# Sensorunit.net
KiCad netlist of a schematic drawn in Altium Designer
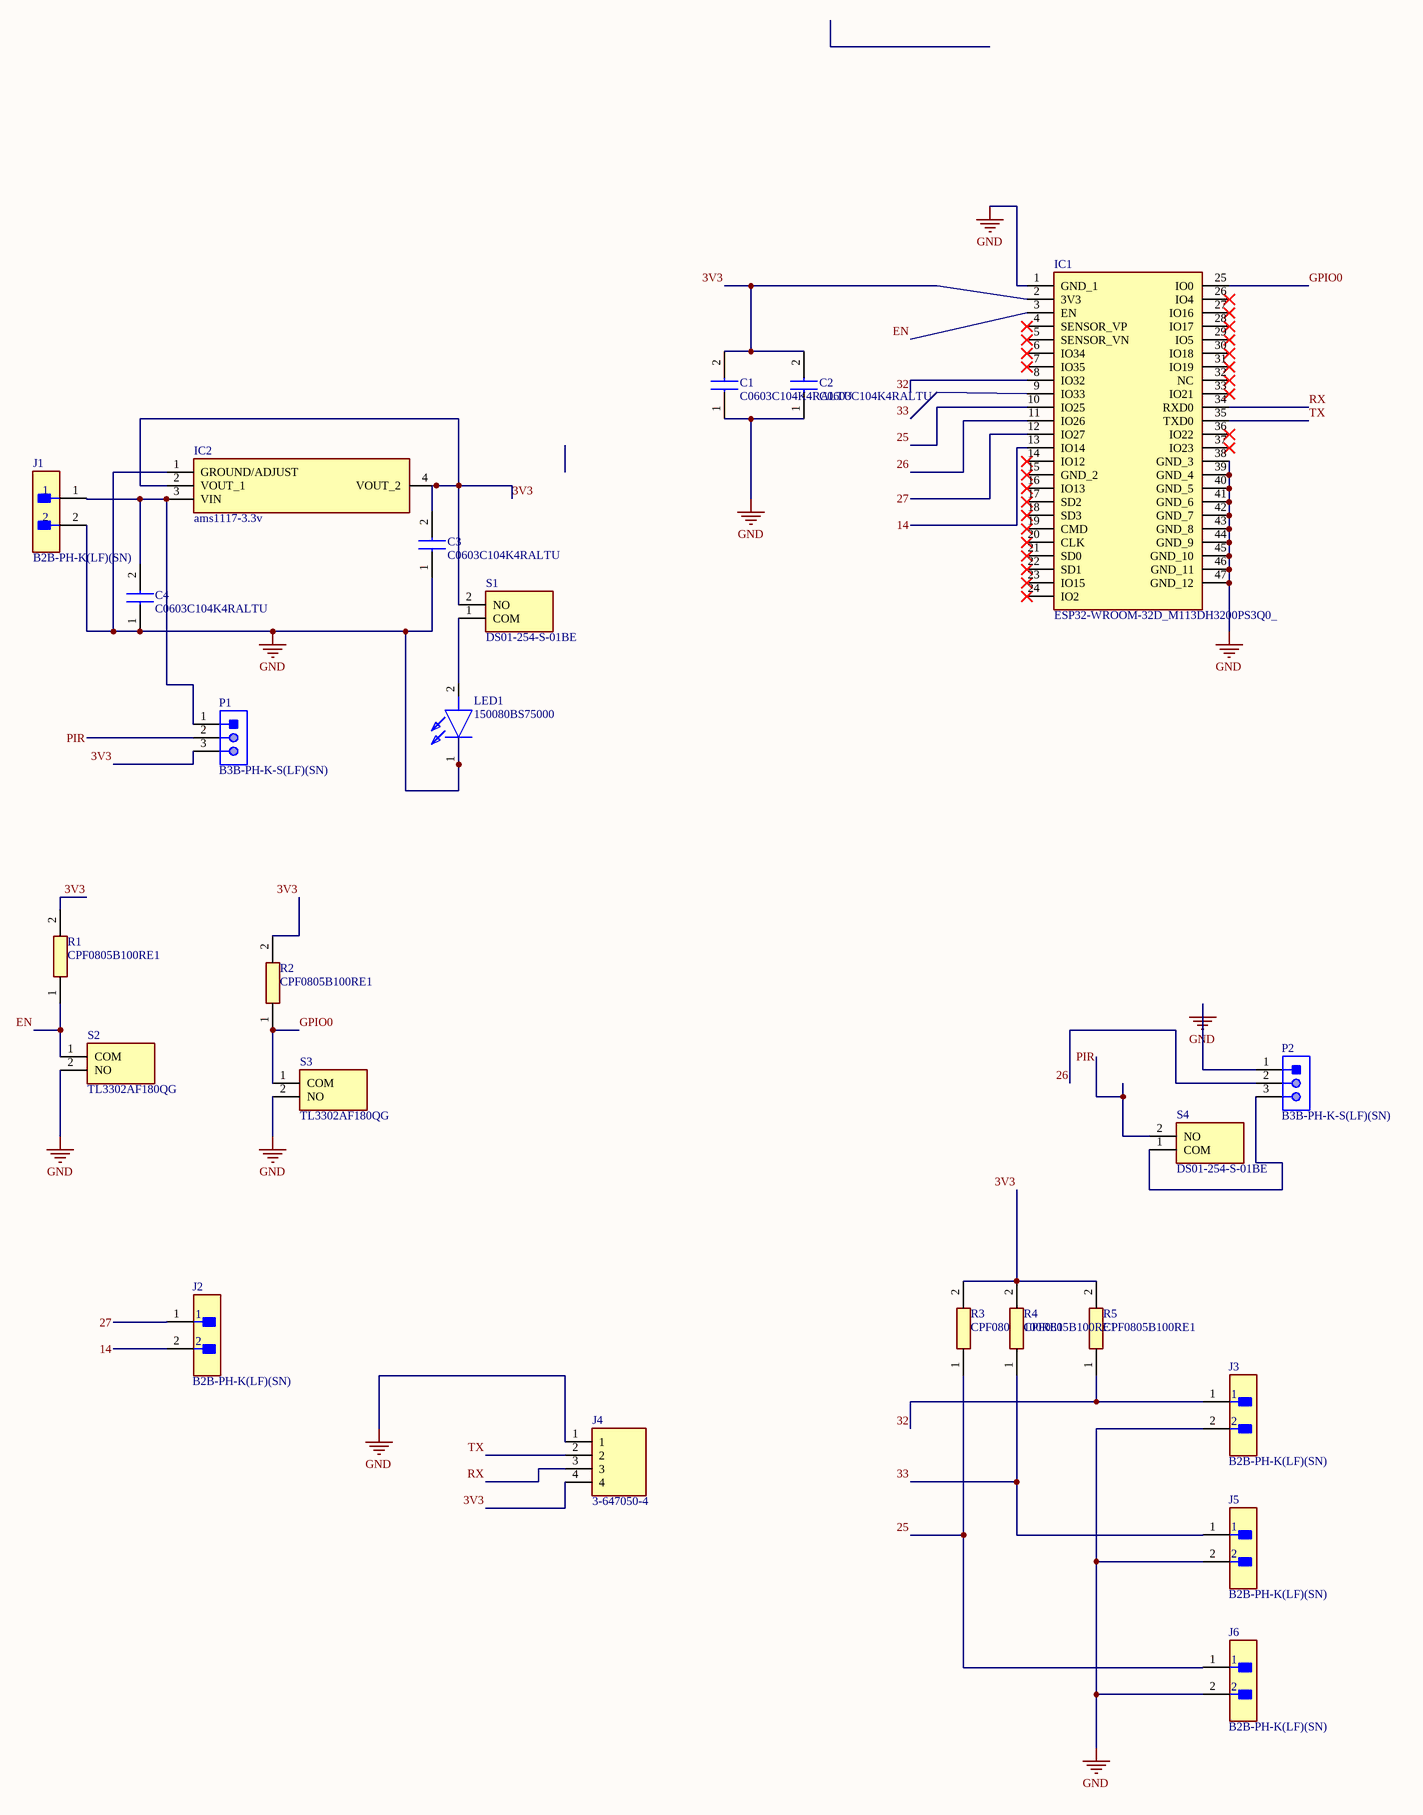
[diagram p0: Sensorunit.SchDoc]

(export (version "E")
  (design (tool "Eeschema 10.0.6"))
  (components
    (comp (ref "C1")
      (value "C0603C104K4RALTU")
      (footprint "SamacSys:C0603")
      (description "Capacitor")
      (fields (field (name "MOUSER PART NUMBER") "80-C0603C104K4RAL"))
      (libsource (lib "SamacSys") (part "C0603C104K4RALTU"))
    )
    (comp (ref "C2")
      (value "C0603C104K4RALTU")
      (footprint "SamacSys:C0603")
      (description "Capacitor")
      (fields (field (name "MOUSER PART NUMBER") "80-C0603C104K4RAL"))
      (libsource (lib "SamacSys") (part "C0603C104K4RALTU"))
    )
    (comp (ref "C3")
      (value "C0603C104K4RALTU")
      (footprint "SamacSys:C0603")
      (description "Capacitor")
      (fields (field (name "MOUSER PART NUMBER") "80-C0603C104K4RAL"))
      (libsource (lib "SamacSys") (part "C0603C104K4RALTU"))
    )
    (comp (ref "C4")
      (value "C0603C104K4RALTU")
      (footprint "SamacSys:C0603")
      (description "Capacitor")
      (fields (field (name "MOUSER PART NUMBER") "80-C0603C104K4RAL"))
      (libsource (lib "SamacSys") (part "C0603C104K4RALTU"))
    )
    (comp (ref "IC1")
      (value "ESP32-WROOM-32D_M113DH3200PS3Q0_")
      (footprint "SamacSys:ESP32WROOM32DM113DH3200PS3Q0")
      (description "Integrated Circuit")
      (fields
        (field (name "MANUFACTURER_PART_NUMBER") "ESP32-WROOM-32D(M113DH3200PS3Q0)")
        (field (name "MOUSER PART NUMBER") "356-ESPWROOM3200PS3")
      )
      (libsource (lib "SamacSys") (part "ESP32-WROOM-32D_M113DH3200PS3Q0_"))
    )
    (comp (ref "IC2")
      (value "ams1117-3.3v")
      (footprint "SamacSys:SOT229P700X180-4N")
      (description "Integrated Circuit")
      (libsource (lib "*") (part "ams1117-3.3v"))
    )
    (comp (ref "J1")
      (value "B2B-PH-K(LF)(SN)")
      (footprint "FP-B2B-PH-K_LF_SN-MFG")
      (description "Connector Header Through Hole 2 position 0.079\" (2.00mm)")
      (libsource (lib "") (part "3bc925449376181038e59eaffc5286c_1"))
    )
    (comp (ref "J2")
      (value "B2B-PH-K(LF)(SN)")
      (footprint "FP-B2B-PH-K_LF_SN-MFG")
      (description "Connector Header Through Hole 2 position 0.079\" (2.00mm)")
      (libsource (lib "Altium Content Vault") (part "3bc925449376181038e59eaffc5286c"))
    )
    (comp (ref "J3")
      (value "B2B-PH-K(LF)(SN)")
      (footprint "FP-B2B-PH-K_LF_SN-MFG")
      (description "Connector Header Through Hole 2 position 0.079\" (2.00mm)")
      (libsource (lib "Altium Content Vault") (part "3bc925449376181038e59eaffc5286c"))
    )
    (comp (ref "J4")
      (value "3-647050-4")
      (footprint "SamacSys:SHDR4W66P0X254_1X4_1016X635X1079P")
      (description "Connector")
      (fields (field (name "MOUSER PART NUMBER") "571-3-647050-4"))
      (libsource (lib "SamacSys") (part "3-647050-4"))
    )
    (comp (ref "J5")
      (value "B2B-PH-K(LF)(SN)")
      (footprint "FP-B2B-PH-K_LF_SN-MFG")
      (description "Connector Header Through Hole 2 position 0.079\" (2.00mm)")
      (libsource (lib "Altium Content Vault") (part "3bc925449376181038e59eaffc5286c"))
    )
    (comp (ref "J6")
      (value "B2B-PH-K(LF)(SN)")
      (footprint "FP-B2B-PH-K_LF_SN-MFG")
      (description "Connector Header Through Hole 2 position 0.079\" (2.00mm)")
      (libsource (lib "Altium Content Vault") (part "3bc925449376181038e59eaffc5286c"))
    )
    (comp (ref "LED1")
      (value "150080BS75000")
      (footprint "SamacSys:LEDC2012X80N")
      (description "LED")
      (fields (field (name "MOUSER PART NUMBER") "710-150080BS75000"))
      (libsource (lib "SamacSys") (part "150080BS75000"))
    )
    (comp (ref "P1")
      (value "B3B-PH-K-S(LF)(SN)")
      (footprint "JST-B3B-PH-K-S-3_V")
      (fields (field (name "MANUFACTURER") "JST"))
      (libsource (lib "Altium Content Vault") (part "CN-1P-M-R3"))
    )
    (comp (ref "P2")
      (value "B3B-PH-K-S(LF)(SN)")
      (footprint "JST-B3B-PH-K-S-3_V")
      (fields (field (name "MANUFACTURER") "JST"))
      (libsource (lib "Altium Content Vault") (part "CN-1P-M-R3"))
    )
    (comp (ref "R1")
      (value "CPF0805B100RE1")
      (footprint "SamacSys:RESC2012X65N")
      (description "Resistor")
      (fields (field (name "MOUSER PART NUMBER") "279-CPF0805B100RE1"))
      (libsource (lib "SamacSys") (part "CPF0805B100RE1"))
    )
    (comp (ref "R2")
      (value "CPF0805B100RE1")
      (footprint "SamacSys:RESC2012X65N")
      (description "Resistor")
      (fields (field (name "MOUSER PART NUMBER") "279-CPF0805B100RE1"))
      (libsource (lib "SamacSys") (part "CPF0805B100RE1"))
    )
    (comp (ref "R3")
      (value "CPF0805B100RE1")
      (footprint "SamacSys:RESC2012X65N")
      (description "Resistor")
      (fields (field (name "MOUSER PART NUMBER") "279-CPF0805B100RE1"))
      (libsource (lib "SamacSys") (part "CPF0805B100RE1"))
    )
    (comp (ref "R4")
      (value "CPF0805B100RE1")
      (footprint "SamacSys:RESC2012X65N")
      (description "Resistor")
      (fields (field (name "MOUSER PART NUMBER") "279-CPF0805B100RE1"))
      (libsource (lib "SamacSys") (part "CPF0805B100RE1"))
    )
    (comp (ref "R5")
      (value "CPF0805B100RE1")
      (footprint "SamacSys:RESC2012X65N")
      (description "Resistor")
      (fields (field (name "MOUSER PART NUMBER") "279-CPF0805B100RE1"))
      (libsource (lib "SamacSys") (part "CPF0805B100RE1"))
    )
    (comp (ref "S1")
      (value "DS01-254-S-01BE")
      (footprint "SamacSys:DS01254S01BE")
      (description "Switch")
      (fields (field (name "MOUSER PART NUMBER") "490-DS01-254-S-01BE"))
      (libsource (lib "*") (part "DS01-254-S-01BE"))
    )
    (comp (ref "S2")
      (value "TL3302AF180QG")
      (footprint "SamacSys:TL3302AF180QG")
      (description "Switch")
      (fields (field (name "MOUSER PART NUMBER") "612-TL3302A"))
      (libsource (lib "SamacSys") (part "TL3302AF180QG"))
    )
    (comp (ref "S3")
      (value "TL3302AF180QG")
      (footprint "SamacSys:TL3302AF180QG")
      (description "Switch")
      (fields (field (name "MOUSER PART NUMBER") "612-TL3302A"))
      (libsource (lib "SamacSys") (part "TL3302AF180QG"))
    )
    (comp (ref "S4")
      (value "DS01-254-S-01BE")
      (footprint "SamacSys:DS01254S01BE")
      (description "Switch")
      (fields (field (name "MOUSER PART NUMBER") "490-DS01-254-S-01BE"))
      (libsource (lib "*") (part "DS01-254-S-01BE"))
    )
  )
  (nets
    (net (code "1") (name "/3V3") (class "Default")
      (node (ref "C1") (pin "2") (pinfunction "2_2") (pintype "passive"))
      (node (ref "C2") (pin "2") (pinfunction "2_2") (pintype "passive"))
      (node (ref "C3") (pin "2") (pinfunction "2_2") (pintype "passive"))
      (node (ref "IC1") (pin "2") (pinfunction "3V3_2") (pintype "passive"))
      (node (ref "IC2") (pin "2") (pinfunction "VOUT_1_2") (pintype "passive"))
      (node (ref "IC2") (pin "4") (pinfunction "VOUT_2_4") (pintype "passive"))
      (node (ref "J4") (pin "4") (pinfunction "4_4") (pintype "passive"))
      (node (ref "P1") (pin "3") (pinfunction "3_3") (pintype "passive"))
      (node (ref "R1") (pin "2") (pinfunction "2_2") (pintype "passive"))
      (node (ref "R2") (pin "2") (pinfunction "2_2") (pintype "passive"))
      (node (ref "R3") (pin "2") (pinfunction "2_2") (pintype "passive"))
      (node (ref "R4") (pin "2") (pinfunction "2_2") (pintype "passive"))
      (node (ref "R5") (pin "2") (pinfunction "2_2") (pintype "passive"))
      (node (ref "S1") (pin "2") (pinfunction "NO_2") (pintype "passive"))
    )
    (net (code "2") (name "/14") (class "Default")
      (node (ref "IC1") (pin "13") (pinfunction "IO14_13") (pintype "passive"))
      (node (ref "J2") (pin "2") (pinfunction "2_2") (pintype "passive"))
    )
    (net (code "3") (name "/25") (class "Default")
      (node (ref "IC1") (pin "10") (pinfunction "IO25_10") (pintype "passive"))
      (node (ref "J6") (pin "1") (pinfunction "1_1") (pintype "passive"))
      (node (ref "R3") (pin "1") (pinfunction "1_1") (pintype "passive"))
    )
    (net (code "4") (name "/26") (class "Default")
      (node (ref "IC1") (pin "11") (pinfunction "IO26_11") (pintype "passive"))
      (node (ref "P2") (pin "2") (pinfunction "2_2") (pintype "passive"))
    )
    (net (code "5") (name "/27") (class "Default")
      (node (ref "IC1") (pin "12") (pinfunction "IO27_12") (pintype "passive"))
      (node (ref "J2") (pin "1") (pinfunction "1_1") (pintype "passive"))
    )
    (net (code "6") (name "/32") (class "Default")
      (node (ref "IC1") (pin "8") (pinfunction "IO32_8") (pintype "passive"))
      (node (ref "J3") (pin "1") (pinfunction "1_1") (pintype "passive"))
      (node (ref "R5") (pin "1") (pinfunction "1_1") (pintype "passive"))
    )
    (net (code "7") (name "/33") (class "Default")
      (node (ref "IC1") (pin "9") (pinfunction "IO33_9") (pintype "passive"))
      (node (ref "J5") (pin "1") (pinfunction "1_1") (pintype "passive"))
      (node (ref "R4") (pin "1") (pinfunction "1_1") (pintype "passive"))
    )
    (net (code "8") (name "/EN") (class "Default")
      (node (ref "IC1") (pin "3") (pinfunction "EN_3") (pintype "passive"))
      (node (ref "R1") (pin "1") (pinfunction "1_1") (pintype "passive"))
      (node (ref "S2") (pin "1") (pinfunction "COM_1") (pintype "passive"))
    )
    (net (code "9") (name "/GPIO0") (class "Default")
      (node (ref "IC1") (pin "25") (pinfunction "IO0_25") (pintype "passive"))
      (node (ref "R2") (pin "1") (pinfunction "1_1") (pintype "passive"))
      (node (ref "S3") (pin "1") (pinfunction "COM_1") (pintype "passive"))
    )
    (net (code "10") (name "/PIR") (class "Default")
      (node (ref "P1") (pin "2") (pinfunction "2_2") (pintype "passive"))
      (node (ref "S4") (pin "2") (pinfunction "NO_2") (pintype "passive"))
    )
    (net (code "11") (name "/RX") (class "Default")
      (node (ref "IC1") (pin "34") (pinfunction "RXD0_34") (pintype "passive"))
      (node (ref "J4") (pin "3") (pinfunction "3_3") (pintype "passive"))
    )
    (net (code "12") (name "/TX") (class "Default")
      (node (ref "IC1") (pin "35") (pinfunction "TXD0_35") (pintype "passive"))
      (node (ref "J4") (pin "2") (pinfunction "2_2") (pintype "passive"))
    )
    (net (code "13") (name "GND") (class "Default")
      (node (ref "C1") (pin "1") (pinfunction "1_1") (pintype "passive"))
      (node (ref "C2") (pin "1") (pinfunction "1_1") (pintype "passive"))
      (node (ref "C3") (pin "1") (pinfunction "1_1") (pintype "passive"))
      (node (ref "C4") (pin "1") (pinfunction "1_1") (pintype "passive"))
      (node (ref "IC1") (pin "1") (pinfunction "GND_1_1") (pintype "passive"))
      (node (ref "IC1") (pin "38") (pinfunction "GND_3_38") (pintype "passive"))
      (node (ref "IC1") (pin "39") (pinfunction "GND_4_39") (pintype "passive"))
      (node (ref "IC1") (pin "40") (pinfunction "GND_5_40") (pintype "passive"))
      (node (ref "IC1") (pin "41") (pinfunction "GND_6_41") (pintype "passive"))
      (node (ref "IC1") (pin "42") (pinfunction "GND_7_42") (pintype "passive"))
      (node (ref "IC1") (pin "43") (pinfunction "GND_8_43") (pintype "passive"))
      (node (ref "IC1") (pin "44") (pinfunction "GND_9_44") (pintype "passive"))
      (node (ref "IC1") (pin "45") (pinfunction "GND_10_45") (pintype "passive"))
      (node (ref "IC1") (pin "46") (pinfunction "GND_11_46") (pintype "passive"))
      (node (ref "IC1") (pin "47") (pinfunction "GND_12_47") (pintype "passive"))
      (node (ref "IC2") (pin "1") (pinfunction "GROUND/ADJUST_1") (pintype "passive"))
      (node (ref "J1") (pin "2") (pinfunction "2_2") (pintype "passive"))
      (node (ref "J3") (pin "2") (pinfunction "2_2") (pintype "passive"))
      (node (ref "J4") (pin "1") (pinfunction "1_1") (pintype "passive"))
      (node (ref "J5") (pin "2") (pinfunction "2_2") (pintype "passive"))
      (node (ref "J6") (pin "2") (pinfunction "2_2") (pintype "passive"))
      (node (ref "LED1") (pin "1") (pinfunction "K_1") (pintype "passive"))
      (node (ref "P2") (pin "1") (pinfunction "1_1") (pintype "passive"))
      (node (ref "S2") (pin "2") (pinfunction "NO_2") (pintype "passive"))
      (node (ref "S3") (pin "2") (pinfunction "NO_2") (pintype "passive"))
    )
    (net (code "14") (name "Net-(IC2-VIN)") (class "Default")
      (node (ref "C4") (pin "2") (pinfunction "2_2") (pintype "passive"))
      (node (ref "IC2") (pin "3") (pinfunction "VIN_3") (pintype "passive"))
      (node (ref "J1") (pin "1") (pinfunction "1_1") (pintype "passive"))
      (node (ref "P1") (pin "1") (pinfunction "1_1") (pintype "passive"))
    )
    (net (code "15") (name "Net-(LED1-A)") (class "Default")
      (node (ref "LED1") (pin "2") (pinfunction "A_2") (pintype "passive"))
      (node (ref "S1") (pin "1") (pinfunction "COM_1") (pintype "passive"))
    )
    (net (code "16") (name "Net-(S4-COM)") (class "Default")
      (node (ref "P2") (pin "3") (pinfunction "3_3") (pintype "passive"))
      (node (ref "S4") (pin "1") (pinfunction "COM_1") (pintype "passive"))
    )
    (net (code "17") (name "unconnected-(IC1-CLK-Pad20)") (class "Default")
      (node (ref "IC1") (pin "20") (pinfunction "CLK_20") (pintype "passive+no_connect"))
    )
    (net (code "18") (name "unconnected-(IC1-CMD-Pad19)") (class "Default")
      (node (ref "IC1") (pin "19") (pinfunction "CMD_19") (pintype "passive+no_connect"))
    )
    (net (code "19") (name "unconnected-(IC1-GND_2-Pad15)") (class "Default")
      (node (ref "IC1") (pin "15") (pinfunction "GND_2_15") (pintype "passive+no_connect"))
    )
    (net (code "20") (name "unconnected-(IC1-IO2-Pad24)") (class "Default")
      (node (ref "IC1") (pin "24") (pinfunction "IO2_24") (pintype "passive+no_connect"))
    )
    (net (code "21") (name "unconnected-(IC1-IO4-Pad26)") (class "Default")
      (node (ref "IC1") (pin "26") (pinfunction "IO4_26") (pintype "passive+no_connect"))
    )
    (net (code "22") (name "unconnected-(IC1-IO5-Pad29)") (class "Default")
      (node (ref "IC1") (pin "29") (pinfunction "IO5_29") (pintype "passive+no_connect"))
    )
    (net (code "23") (name "unconnected-(IC1-IO12-Pad14)") (class "Default")
      (node (ref "IC1") (pin "14") (pinfunction "IO12_14") (pintype "passive+no_connect"))
    )
    (net (code "24") (name "unconnected-(IC1-IO13-Pad16)") (class "Default")
      (node (ref "IC1") (pin "16") (pinfunction "IO13_16") (pintype "passive+no_connect"))
    )
    (net (code "25") (name "unconnected-(IC1-IO15-Pad23)") (class "Default")
      (node (ref "IC1") (pin "23") (pinfunction "IO15_23") (pintype "passive+no_connect"))
    )
    (net (code "26") (name "unconnected-(IC1-IO16-Pad27)") (class "Default")
      (node (ref "IC1") (pin "27") (pinfunction "IO16_27") (pintype "passive+no_connect"))
    )
    (net (code "27") (name "unconnected-(IC1-IO17-Pad28)") (class "Default")
      (node (ref "IC1") (pin "28") (pinfunction "IO17_28") (pintype "passive+no_connect"))
    )
    (net (code "28") (name "unconnected-(IC1-IO18-Pad30)") (class "Default")
      (node (ref "IC1") (pin "30") (pinfunction "IO18_30") (pintype "passive+no_connect"))
    )
    (net (code "29") (name "unconnected-(IC1-IO19-Pad31)") (class "Default")
      (node (ref "IC1") (pin "31") (pinfunction "IO19_31") (pintype "passive+no_connect"))
    )
    (net (code "30") (name "unconnected-(IC1-IO21-Pad33)") (class "Default")
      (node (ref "IC1") (pin "33") (pinfunction "IO21_33") (pintype "passive+no_connect"))
    )
    (net (code "31") (name "unconnected-(IC1-IO22-Pad36)") (class "Default")
      (node (ref "IC1") (pin "36") (pinfunction "IO22_36") (pintype "passive+no_connect"))
    )
    (net (code "32") (name "unconnected-(IC1-IO23-Pad37)") (class "Default")
      (node (ref "IC1") (pin "37") (pinfunction "IO23_37") (pintype "passive+no_connect"))
    )
    (net (code "33") (name "unconnected-(IC1-IO34-Pad6)") (class "Default")
      (node (ref "IC1") (pin "6") (pinfunction "IO34_6") (pintype "passive+no_connect"))
    )
    (net (code "34") (name "unconnected-(IC1-IO35-Pad7)") (class "Default")
      (node (ref "IC1") (pin "7") (pinfunction "IO35_7") (pintype "passive+no_connect"))
    )
    (net (code "35") (name "unconnected-(IC1-NC-Pad32)") (class "Default")
      (node (ref "IC1") (pin "32") (pinfunction "NC_32") (pintype "passive+no_connect"))
    )
    (net (code "36") (name "unconnected-(IC1-SD0-Pad21)") (class "Default")
      (node (ref "IC1") (pin "21") (pinfunction "SD0_21") (pintype "passive+no_connect"))
    )
    (net (code "37") (name "unconnected-(IC1-SD1-Pad22)") (class "Default")
      (node (ref "IC1") (pin "22") (pinfunction "SD1_22") (pintype "passive+no_connect"))
    )
    (net (code "38") (name "unconnected-(IC1-SD2-Pad17)") (class "Default")
      (node (ref "IC1") (pin "17") (pinfunction "SD2_17") (pintype "passive+no_connect"))
    )
    (net (code "39") (name "unconnected-(IC1-SD3-Pad18)") (class "Default")
      (node (ref "IC1") (pin "18") (pinfunction "SD3_18") (pintype "passive+no_connect"))
    )
    (net (code "40") (name "unconnected-(IC1-SENSOR_VN-Pad5)") (class "Default")
      (node (ref "IC1") (pin "5") (pinfunction "SENSOR_VN_5") (pintype "passive+no_connect"))
    )
    (net (code "41") (name "unconnected-(IC1-SENSOR_VP-Pad4)") (class "Default")
      (node (ref "IC1") (pin "4") (pinfunction "SENSOR_VP_4") (pintype "passive+no_connect"))
    )
  )
)
